# MCU.net
KiCad netlist of a schematic drawn in Altium Designer
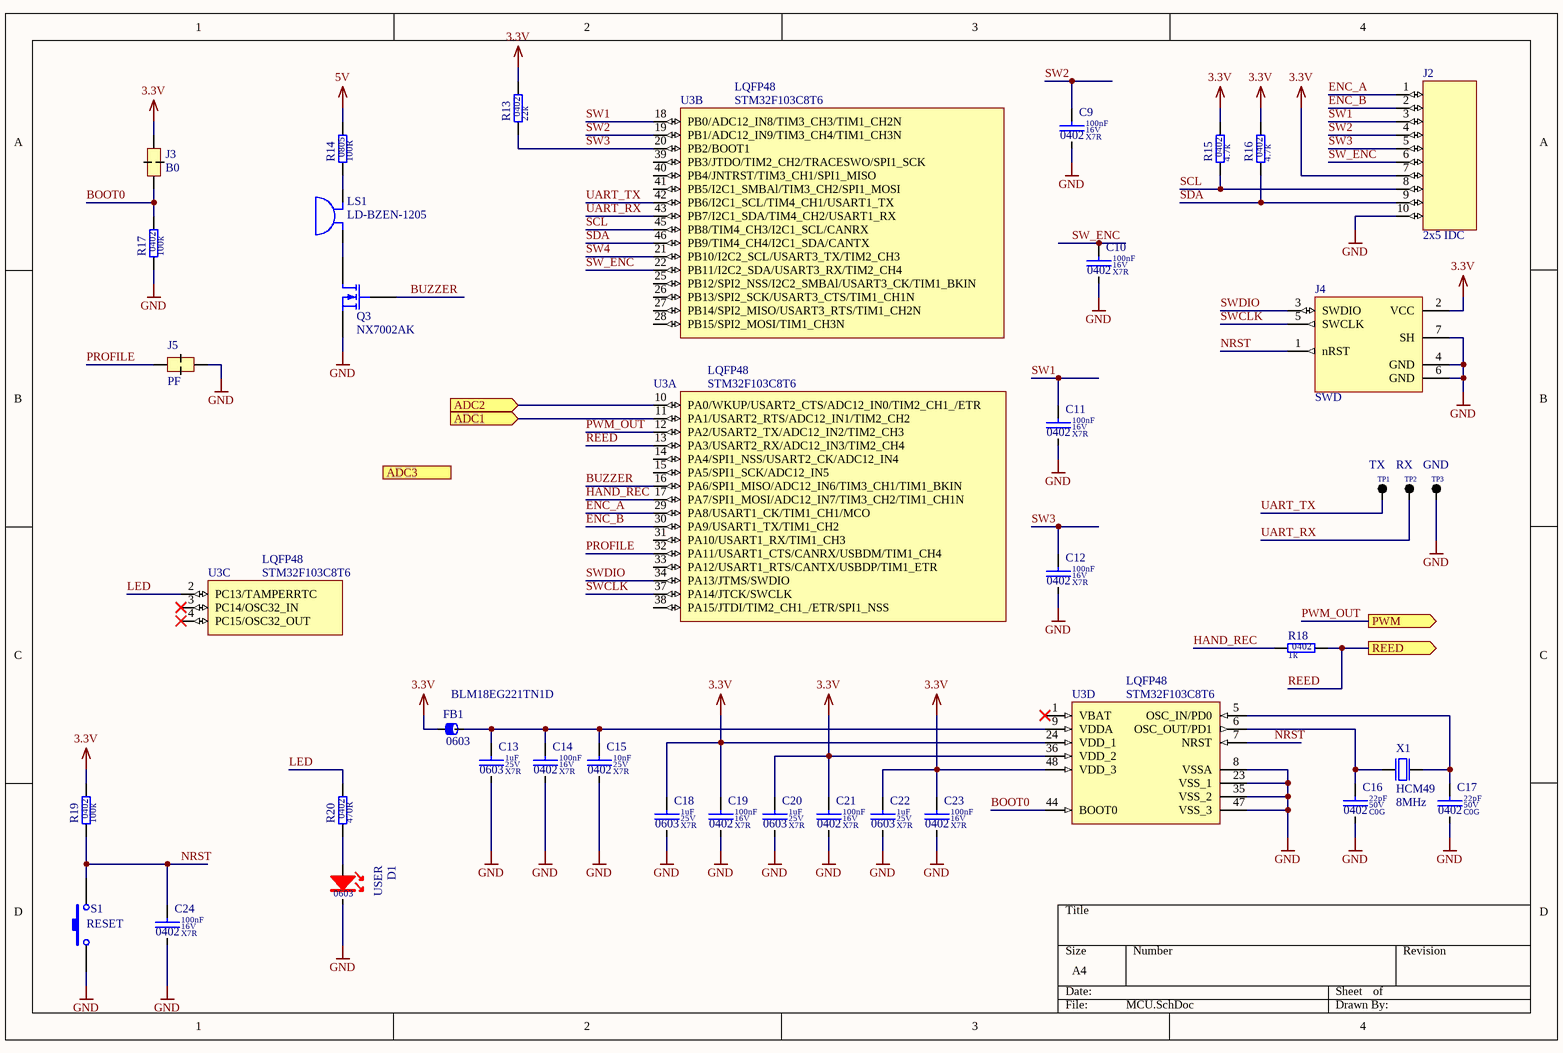
[diagram p0: MCU.SchDoc]

(export (version "E")
  (design (tool "Eeschema 10.0.6"))
  (components
    (comp (ref "C9")
      (value "100nF")
      (footprint "C_0402_1005")
      (description "Capacitor")
      (fields
        (field (name "DIELECTRIC") "X7R")
        (field (name "VOLTAGE") "16V")
        (field (name "SCH_FOOTPRINT") "0402")
        (field (name "PART NUMBER") "C_100nF_16V_X7R_0402_10")
        (field (name "MANUFACTURER") "Murata")
      )
      (libsource (lib "Library") (part "C"))
    )
    (comp (ref "C10")
      (value "100nF")
      (footprint "C_0402_1005")
      (description "Capacitor")
      (fields
        (field (name "DIELECTRIC") "X7R")
        (field (name "VOLTAGE") "16V")
        (field (name "SCH_FOOTPRINT") "0402")
        (field (name "PART NUMBER") "C_100nF_16V_X7R_0402_10")
        (field (name "MANUFACTURER") "Murata")
      )
      (libsource (lib "Library") (part "C"))
    )
    (comp (ref "C11")
      (value "100nF")
      (footprint "C_0402_1005")
      (description "Capacitor")
      (fields
        (field (name "DIELECTRIC") "X7R")
        (field (name "VOLTAGE") "16V")
        (field (name "SCH_FOOTPRINT") "0402")
        (field (name "PART NUMBER") "C_100nF_16V_X7R_0402_10")
        (field (name "MANUFACTURER") "Murata")
      )
      (libsource (lib "Library") (part "C"))
    )
    (comp (ref "C12")
      (value "100nF")
      (footprint "C_0402_1005")
      (description "Capacitor")
      (fields
        (field (name "DIELECTRIC") "X7R")
        (field (name "VOLTAGE") "16V")
        (field (name "SCH_FOOTPRINT") "0402")
        (field (name "PART NUMBER") "C_100nF_16V_X7R_0402_10")
        (field (name "MANUFACTURER") "Murata")
      )
      (libsource (lib "Library") (part "C"))
    )
    (comp (ref "C13")
      (value "1uF")
      (footprint "C_0603_1608")
      (description "Capacitor")
      (fields
        (field (name "DIELECTRIC") "X7R")
        (field (name "VOLTAGE") "25V")
        (field (name "SCH_FOOTPRINT") "0603")
        (field (name "PART NUMBER") "C_1uF_25V_X7R_0603_10")
        (field (name "MANUFACTURER") "Samsung")
      )
      (libsource (lib "Library") (part "C"))
    )
    (comp (ref "C14")
      (value "100nF")
      (footprint "C_0402_1005")
      (description "Capacitor")
      (fields
        (field (name "DIELECTRIC") "X7R")
        (field (name "VOLTAGE") "16V")
        (field (name "SCH_FOOTPRINT") "0402")
        (field (name "PART NUMBER") "C_100nF_16V_X7R_0402_10")
        (field (name "MANUFACTURER") "Murata")
      )
      (libsource (lib "Library") (part "C"))
    )
    (comp (ref "C15")
      (value "10nF")
      (footprint "C_0402_1005")
      (description "Capacitor")
      (fields
        (field (name "DIELECTRIC") "X7R")
        (field (name "VOLTAGE") "25V")
        (field (name "SCH_FOOTPRINT") "0402")
        (field (name "PART NUMBER") "C_10nF_25V_X7R_0402_10")
        (field (name "MANUFACTURER") "Murata")
      )
      (libsource (lib "Library") (part "C"))
    )
    (comp (ref "C16")
      (value "22pF")
      (footprint "C_0402_1005")
      (description "Capacitor")
      (fields
        (field (name "DIELECTRIC") "C0G")
        (field (name "VOLTAGE") "50V")
        (field (name "SCH_FOOTPRINT") "0402")
        (field (name "PART NUMBER") "C_22pF_50V_C0G_0402_5")
        (field (name "MANUFACTURER") "AVX")
      )
      (libsource (lib "Library") (part "C"))
    )
    (comp (ref "C17")
      (value "22pF")
      (footprint "C_0402_1005")
      (description "Capacitor")
      (fields
        (field (name "DIELECTRIC") "C0G")
        (field (name "VOLTAGE") "50V")
        (field (name "SCH_FOOTPRINT") "0402")
        (field (name "PART NUMBER") "C_22pF_50V_C0G_0402_5")
        (field (name "MANUFACTURER") "AVX")
      )
      (libsource (lib "Library") (part "C"))
    )
    (comp (ref "C18")
      (value "1uF")
      (footprint "C_0603_1608")
      (description "Capacitor")
      (fields
        (field (name "DIELECTRIC") "X7R")
        (field (name "VOLTAGE") "25V")
        (field (name "SCH_FOOTPRINT") "0603")
        (field (name "PART NUMBER") "C_1uF_25V_X7R_0603_10")
        (field (name "MANUFACTURER") "Samsung")
      )
      (libsource (lib "Library") (part "C"))
    )
    (comp (ref "C19")
      (value "100nF")
      (footprint "C_0402_1005")
      (description "Capacitor")
      (fields
        (field (name "DIELECTRIC") "X7R")
        (field (name "VOLTAGE") "16V")
        (field (name "SCH_FOOTPRINT") "0402")
        (field (name "PART NUMBER") "C_100nF_16V_X7R_0402_10")
        (field (name "MANUFACTURER") "Murata")
      )
      (libsource (lib "Library") (part "C"))
    )
    (comp (ref "C20")
      (value "1uF")
      (footprint "C_0603_1608")
      (description "Capacitor")
      (fields
        (field (name "DIELECTRIC") "X7R")
        (field (name "VOLTAGE") "25V")
        (field (name "SCH_FOOTPRINT") "0603")
        (field (name "PART NUMBER") "C_1uF_25V_X7R_0603_10")
        (field (name "MANUFACTURER") "Samsung")
      )
      (libsource (lib "Library") (part "C"))
    )
    (comp (ref "C21")
      (value "100nF")
      (footprint "C_0402_1005")
      (description "Capacitor")
      (fields
        (field (name "DIELECTRIC") "X7R")
        (field (name "VOLTAGE") "16V")
        (field (name "SCH_FOOTPRINT") "0402")
        (field (name "PART NUMBER") "C_100nF_16V_X7R_0402_10")
        (field (name "MANUFACTURER") "Murata")
      )
      (libsource (lib "Library") (part "C"))
    )
    (comp (ref "C22")
      (value "1uF")
      (footprint "C_0603_1608")
      (description "Capacitor")
      (fields
        (field (name "DIELECTRIC") "X7R")
        (field (name "VOLTAGE") "25V")
        (field (name "SCH_FOOTPRINT") "0603")
        (field (name "PART NUMBER") "C_1uF_25V_X7R_0603_10")
        (field (name "MANUFACTURER") "Samsung")
      )
      (libsource (lib "Library") (part "C"))
    )
    (comp (ref "C23")
      (value "100nF")
      (footprint "C_0402_1005")
      (description "Capacitor")
      (fields
        (field (name "DIELECTRIC") "X7R")
        (field (name "VOLTAGE") "16V")
        (field (name "SCH_FOOTPRINT") "0402")
        (field (name "PART NUMBER") "C_100nF_16V_X7R_0402_10")
        (field (name "MANUFACTURER") "Murata")
      )
      (libsource (lib "Library") (part "C"))
    )
    (comp (ref "C24")
      (value "100nF")
      (footprint "C_0402_1005")
      (description "Capacitor")
      (fields
        (field (name "DIELECTRIC") "X7R")
        (field (name "VOLTAGE") "16V")
        (field (name "SCH_FOOTPRINT") "0402")
        (field (name "PART NUMBER") "C_100nF_16V_X7R_0402_10")
        (field (name "MANUFACTURER") "Murata")
      )
      (libsource (lib "Library") (part "C"))
    )
    (comp (ref "D1")
      (value "USER")
      (footprint "OL_0603_1608")
      (description "LED_RED")
      (fields
        (field (name "SCH_FOOTPRINT") "0603")
        (field (name "PART NUMBER") "OL_R_0603")
        (field (name "MANUFACTURER") "Lite-On")
      )
      (libsource (lib "Library") (part "OL_R"))
    )
    (comp (ref "FB1")
      (value "BLM18EG221TN1D")
      (footprint "FB_0603_1608")
      (description "Ferrite Bead")
      (fields
        (field (name "PART NUMBER") "FB_BLM18EG221TN1D")
        (field (name "SCH_FOOTPRINT") "0603")
        (field (name "MANUFACTURER") "Murata")
      )
      (libsource (lib "Library") (part "FB"))
    )
    (comp (ref "J2")
      (value "2x5 IDC")
      (footprint "IDC 2x5 EDGE")
      (description "2x5 IDC Header")
      (libsource (lib "Lib - Connectors") (part "IDC_2x5"))
    )
    (comp (ref "J3")
      (value "B0")
      (footprint "SOLDER BRIDGE 0402")
      (description "Solder Bridge Jumper")
      (libsource (lib "Lib - Connectors") (part "Solder Bridge"))
    )
    (comp (ref "J4")
      (value "SWD")
      (footprint "TagConnectSWD")
      (description "TagConnect and 1.27mm IDC SWD Header")
      (libsource (lib "Lib - Connectors") (part "TagConnectSWD"))
    )
    (comp (ref "J5")
      (value "PF")
      (footprint "SOLDER BRIDGE 0402")
      (description "Solder Bridge Jumper")
      (libsource (lib "") (part "Solder Bridge_1"))
    )
    (comp (ref "LS1")
      (value "LD-BZEN-1205")
      (footprint "LD-BZEN-1205")
      (description "Przetwornik dźwięku: elektromagnetyczny; THT; 2,4kHz; 40mA; H: 9mm")
      (libsource (lib "soldering_station") (part "LD-BZEN-1205"))
    )
    (comp (ref "Q3")
      (value "NX7002AK")
      (footprint "NX7002AK.215")
      (description "Tranzystor: N-MOSFET; unipolarny; 60V; 0,12A; 325mW; SOT23")
      (libsource (lib "soldering_station") (part "NX7002AK.215"))
    )
    (comp (ref "R13")
      (value "22k")
      (footprint "R_0402_1005")
      (fields
        (field (name "SCH_FOOTPRINT") "0402")
        (field (name "PART NUMBER") "R_22k_0402_1")
        (field (name "VOLTAGE") "50V")
        (field (name "POWER") "63mW")
      )
      (libsource (lib "Library") (part "R"))
    )
    (comp (ref "R14")
      (value "100R")
      (footprint "R_0805_2012")
      (fields
        (field (name "SCH_FOOTPRINT") "0805")
        (field (name "PART NUMBER") "R_100R_0805_1")
        (field (name "VOLTAGE") "150V")
        (field (name "POWER") "125mW")
      )
      (libsource (lib "Library") (part "R"))
    )
    (comp (ref "R15")
      (value "4.7k")
      (footprint "R_0402_1005")
      (fields
        (field (name "SCH_FOOTPRINT") "0402")
        (field (name "PART NUMBER") "R_100k_0402_1")
        (field (name "VOLTAGE") "50V")
        (field (name "POWER") "63mW")
      )
      (libsource (lib "Library") (part "R"))
    )
    (comp (ref "R16")
      (value "4.7k")
      (footprint "R_0402_1005")
      (fields
        (field (name "SCH_FOOTPRINT") "0402")
        (field (name "PART NUMBER") "R_100k_0402_1")
        (field (name "VOLTAGE") "50V")
        (field (name "POWER") "63mW")
      )
      (libsource (lib "Library") (part "R"))
    )
    (comp (ref "R17")
      (value "100k")
      (footprint "R_0402_1005")
      (fields
        (field (name "SCH_FOOTPRINT") "0402")
        (field (name "PART NUMBER") "R_100k_0402_1")
        (field (name "VOLTAGE") "50V")
        (field (name "POWER") "63mW")
      )
      (libsource (lib "Library") (part "R"))
    )
    (comp (ref "R18")
      (value "1k")
      (footprint "R_0402_1005")
      (fields
        (field (name "SCH_FOOTPRINT") "0402")
        (field (name "PART NUMBER") "R_1k_0402_1")
        (field (name "VOLTAGE") "50V")
        (field (name "POWER") "63mW")
      )
      (libsource (lib "Library") (part "R"))
    )
    (comp (ref "R19")
      (value "100k")
      (footprint "R_0402_1005")
      (fields
        (field (name "SCH_FOOTPRINT") "0402")
        (field (name "PART NUMBER") "R_100k_0402_1")
        (field (name "VOLTAGE") "50V")
        (field (name "POWER") "63mW")
      )
      (libsource (lib "Library") (part "R"))
    )
    (comp (ref "R20")
      (value "470R")
      (footprint "R_0402_1005")
      (fields
        (field (name "SCH_FOOTPRINT") "0402")
        (field (name "PART NUMBER") "R_470R_0402_1")
        (field (name "VOLTAGE") "50V")
        (field (name "POWER") "63mW")
      )
      (libsource (lib "Library") (part "R"))
    )
    (comp (ref "S1")
      (value "RESET")
      (footprint "S_TACTSWITCH3x6")
      (description "Tact Switch")
      (fields (field (name "PART NUMBER") "S_TACTSWITCH") (field (name "MANUFACTURER") "Ninigi"))
      (libsource (lib "Library") (part "S_TACTSWITCH"))
    )
    (comp (ref "TP1")
      (value "TX")
      (footprint "TP_PAD")
      (description "Testpoint")
      (fields (field (name "PART NUMBER") "TP_PAD"))
      (libsource (lib "Library") (part "TP_TESTPOINT"))
    )
    (comp (ref "TP2")
      (value "RX")
      (footprint "TP_PAD")
      (description "Testpoint")
      (fields (field (name "PART NUMBER") "TP_PAD"))
      (libsource (lib "Library") (part "TP_TESTPOINT"))
    )
    (comp (ref "TP3")
      (value "GND")
      (footprint "TP_PAD")
      (description "Testpoint")
      (fields (field (name "PART NUMBER") "TP_PAD"))
      (libsource (lib "Library") (part "TP_TESTPOINT"))
    )
    (comp (ref "U3")
      (value "STM32F103C8T6")
      (footprint "LQFP48_7x7")
      (fields
        (field (name "SCH_FOOTPRINT") "LQFP48")
        (field (name "PART NUMBER") "UP_STM32F103C8T6")
        (field (name "MANUFACTURER") "STMicroelectronics")
      )
      (libsource (lib "Library") (part "UP_STM32F103Cx"))
    )
    (comp (ref "X1")
      (value "8MHz")
      (footprint "X_HC49_SMD")
      (description "Resonator Ceramic")
      (fields
        (field (name "SCH_FOOTPRINT") "HCM49")
        (field (name "PART NUMBER") "X_6MHz_HCM49")
        (field (name "MANUFACTURER PART NUMBER") "LF XTAL016788")
      )
      (libsource (lib "Library") (part "X_GENERIC"))
    )
  )
  (nets
    (net (code "1") (name "/ADC1") (class "Default")
      (node (ref "U3") (pin "11") (pinfunction "PA1/USART2_RTS/ADC12_IN1/TIM2_CH2_11") (pintype "bidirectional"))
    )
    (net (code "2") (name "/ADC2") (class "Default")
      (node (ref "U3") (pin "10") (pinfunction "PA0/WKUP/USART2_CTS/ADC12_IN0/TIM2_CH1_/ETR_10") (pintype "bidirectional"))
    )
    (net (code "4") (name "/BOOT0") (class "Default")
      (node (ref "J3") (pin "2") (pinfunction "2_2") (pintype "passive"))
      (node (ref "R17") (pin "2") (pinfunction "2_2") (pintype "passive"))
      (node (ref "U3") (pin "44") (pinfunction "BOOT0_44") (pintype "input"))
    )
    (net (code "5") (name "/BUZZER") (class "Default")
      (node (ref "Q3") (pin "1") (pinfunction "G_1") (pintype "passive"))
      (node (ref "U3") (pin "16") (pinfunction "PA6/SPI1_MISO/ADC12_IN6/TIM3_CH1/TIM1_BKIN_16") (pintype "bidirectional"))
    )
    (net (code "6") (name "/ENC_A") (class "Default")
      (node (ref "J2") (pin "1") (pintype "bidirectional"))
      (node (ref "U3") (pin "29") (pinfunction "PA8/USART1_CK/TIM1_CH1/MCO_29") (pintype "bidirectional"))
    )
    (net (code "7") (name "/ENC_B") (class "Default")
      (node (ref "J2") (pin "2") (pintype "bidirectional"))
      (node (ref "U3") (pin "30") (pinfunction "PA9/USART1_TX/TIM1_CH2_30") (pintype "bidirectional"))
    )
    (net (code "8") (name "/HAND_REC") (class "Default")
      (node (ref "R18") (pin "1") (pinfunction "1_1") (pintype "passive"))
      (node (ref "U3") (pin "17") (pinfunction "PA7/SPI1_MOSI/ADC12_IN7/TIM3_CH2/TIM1_CH1N_17") (pintype "bidirectional"))
    )
    (net (code "9") (name "/LED") (class "Default")
      (node (ref "R20") (pin "2") (pinfunction "2_2") (pintype "passive"))
      (node (ref "U3") (pin "2") (pinfunction "PC13/TAMPERRTC_2") (pintype "bidirectional"))
    )
    (net (code "10") (name "/NRST") (class "Default")
      (node (ref "C24") (pin "1") (pinfunction "1_1") (pintype "passive"))
      (node (ref "J4") (pin "1") (pinfunction "nRST_1") (pintype "output"))
      (node (ref "R19") (pin "1") (pinfunction "1_1") (pintype "passive"))
      (node (ref "S1") (pin "2") (pinfunction "2_2") (pintype "passive"))
      (node (ref "U3") (pin "7") (pinfunction "NRST_7") (pintype "input"))
    )
    (net (code "11") (name "/PROFILE") (class "Default")
      (node (ref "J5") (pin "2") (pinfunction "2_2") (pintype "passive"))
      (node (ref "U3") (pin "32") (pinfunction "PA11/USART1_CTS/CANRX/USBDM/TIM1_CH4_32") (pintype "bidirectional"))
    )
    (net (code "12") (name "/PWM_OUT") (class "Default")
      (node (ref "U3") (pin "12") (pinfunction "PA2/USART2_TX/ADC12_IN2/TIM2_CH3_12") (pintype "bidirectional"))
    )
    (net (code "13") (name "/REED") (class "Default")
      (node (ref "R18") (pin "2") (pinfunction "2_2") (pintype "passive"))
      (node (ref "U3") (pin "13") (pinfunction "PA3/USART2_RX/ADC12_IN3/TIM2_CH4_13") (pintype "bidirectional"))
    )
    (net (code "14") (name "/SCL") (class "Default")
      (node (ref "J2") (pin "8") (pintype "bidirectional"))
      (node (ref "R15") (pin "1") (pinfunction "1_1") (pintype "passive"))
      (node (ref "U3") (pin "45") (pinfunction "PB8/TIM4_CH3/I2C1_SCL/CANRX_45") (pintype "bidirectional"))
    )
    (net (code "15") (name "/SDA") (class "Default")
      (node (ref "J2") (pin "9") (pintype "bidirectional"))
      (node (ref "R16") (pin "1") (pinfunction "1_1") (pintype "passive"))
      (node (ref "U3") (pin "46") (pinfunction "PB9/TIM4_CH4/I2C1_SDA/CANTX_46") (pintype "bidirectional"))
    )
    (net (code "16") (name "/SW1") (class "Default")
      (node (ref "C11") (pin "1") (pinfunction "1_1") (pintype "passive"))
      (node (ref "J2") (pin "3") (pintype "bidirectional"))
      (node (ref "U3") (pin "18") (pinfunction "PB0/ADC12_IN8/TIM3_CH3/TIM1_CH2N_18") (pintype "bidirectional"))
    )
    (net (code "17") (name "/SW2") (class "Default")
      (node (ref "C9") (pin "1") (pinfunction "1_1") (pintype "passive"))
      (node (ref "J2") (pin "4") (pintype "bidirectional"))
      (node (ref "U3") (pin "19") (pinfunction "PB1/ADC12_IN9/TIM3_CH4/TIM1_CH3N_19") (pintype "bidirectional"))
    )
    (net (code "18") (name "/SW3") (class "Default")
      (node (ref "C12") (pin "1") (pinfunction "1_1") (pintype "passive"))
      (node (ref "J2") (pin "5") (pintype "bidirectional"))
      (node (ref "R13") (pin "1") (pinfunction "1_1") (pintype "passive"))
      (node (ref "U3") (pin "20") (pinfunction "PB2/BOOT1_20") (pintype "bidirectional"))
    )
    (net (code "19") (name "/SW4") (class "Default")
      (node (ref "U3") (pin "21") (pinfunction "PB10/I2C2_SCL/USART3_TX/TIM2_CH3_21") (pintype "bidirectional"))
    )
    (net (code "20") (name "/SWCLK") (class "Default")
      (node (ref "J4") (pin "5") (pinfunction "SWCLK_5") (pintype "output"))
      (node (ref "U3") (pin "37") (pinfunction "PA14/JTCK/SWCLK_37") (pintype "bidirectional"))
    )
    (net (code "21") (name "/SWDIO") (class "Default")
      (node (ref "J4") (pin "3") (pinfunction "SWDIO_3") (pintype "bidirectional"))
      (node (ref "U3") (pin "34") (pinfunction "PA13/JTMS/SWDIO_34") (pintype "bidirectional"))
    )
    (net (code "22") (name "/SW_ENC") (class "Default")
      (node (ref "C10") (pin "1") (pinfunction "1_1") (pintype "passive"))
      (node (ref "J2") (pin "6") (pintype "bidirectional"))
      (node (ref "U3") (pin "22") (pinfunction "PB11/I2C2_SDA/USART3_RX/TIM2_CH4_22") (pintype "bidirectional"))
    )
    (net (code "23") (name "/UART_RX") (class "Default")
      (node (ref "TP2") (pin "1") (pinfunction "TP_1") (pintype "passive"))
      (node (ref "U3") (pin "43") (pinfunction "PB7/I2C1_SDA/TIM4_CH2/USART1_RX_43") (pintype "bidirectional"))
    )
    (net (code "24") (name "/UART_TX") (class "Default")
      (node (ref "TP1") (pin "1") (pinfunction "TP_1") (pintype "passive"))
      (node (ref "U3") (pin "42") (pinfunction "PB6/I2C1_SCL/TIM4_CH1/USART1_TX_42") (pintype "bidirectional"))
    )
    (net (code "25") (name "3.3V") (class "Default")
      (node (ref "C18") (pin "1") (pinfunction "1_1") (pintype "passive"))
      (node (ref "C19") (pin "1") (pinfunction "1_1") (pintype "passive"))
      (node (ref "C20") (pin "1") (pinfunction "1_1") (pintype "passive"))
      (node (ref "C21") (pin "1") (pinfunction "1_1") (pintype "passive"))
      (node (ref "C22") (pin "1") (pinfunction "1_1") (pintype "passive"))
      (node (ref "C23") (pin "1") (pinfunction "1_1") (pintype "passive"))
      (node (ref "FB1") (pin "1") (pintype "passive"))
      (node (ref "J2") (pin "7") (pintype "bidirectional"))
      (node (ref "J3") (pin "1") (pinfunction "1_1") (pintype "passive"))
      (node (ref "J4") (pin "2") (pinfunction "VCC_2") (pintype "power_in"))
      (node (ref "R13") (pin "2") (pinfunction "2_2") (pintype "passive"))
      (node (ref "R15") (pin "2") (pinfunction "2_2") (pintype "passive"))
      (node (ref "R16") (pin "2") (pinfunction "2_2") (pintype "passive"))
      (node (ref "R19") (pin "2") (pinfunction "2_2") (pintype "passive"))
      (node (ref "U3") (pin "24") (pinfunction "VDD_1_24") (pintype "input"))
      (node (ref "U3") (pin "36") (pinfunction "VDD_2_36") (pintype "input"))
      (node (ref "U3") (pin "48") (pinfunction "VDD_3_48") (pintype "input"))
    )
    (net (code "26") (name "5V") (class "Default")
      (node (ref "R14") (pin "2") (pinfunction "2_2") (pintype "passive"))
    )
    (net (code "27") (name "GND") (class "Default")
      (node (ref "C10") (pin "2") (pinfunction "2_2") (pintype "passive"))
      (node (ref "C11") (pin "2") (pinfunction "2_2") (pintype "passive"))
      (node (ref "C12") (pin "2") (pinfunction "2_2") (pintype "passive"))
      (node (ref "C13") (pin "2") (pinfunction "2_2") (pintype "passive"))
      (node (ref "C14") (pin "2") (pinfunction "2_2") (pintype "passive"))
      (node (ref "C15") (pin "2") (pinfunction "2_2") (pintype "passive"))
      (node (ref "C16") (pin "2") (pinfunction "2_2") (pintype "passive"))
      (node (ref "C17") (pin "2") (pinfunction "2_2") (pintype "passive"))
      (node (ref "C18") (pin "2") (pinfunction "2_2") (pintype "passive"))
      (node (ref "C19") (pin "2") (pinfunction "2_2") (pintype "passive"))
      (node (ref "C20") (pin "2") (pinfunction "2_2") (pintype "passive"))
      (node (ref "C21") (pin "2") (pinfunction "2_2") (pintype "passive"))
      (node (ref "C22") (pin "2") (pinfunction "2_2") (pintype "passive"))
      (node (ref "C23") (pin "2") (pinfunction "2_2") (pintype "passive"))
      (node (ref "C24") (pin "2") (pinfunction "2_2") (pintype "passive"))
      (node (ref "C9") (pin "2") (pinfunction "2_2") (pintype "passive"))
      (node (ref "D1") (pin "1") (pinfunction "K_1") (pintype "passive"))
      (node (ref "J2") (pin "10") (pintype "bidirectional"))
      (node (ref "J4") (pin "4") (pinfunction "GND_4") (pintype "power_in"))
      (node (ref "J4") (pin "6") (pinfunction "GND_6") (pintype "power_in"))
      (node (ref "J4") (pin "7") (pinfunction "SH_7") (pintype "passive"))
      (node (ref "J5") (pin "1") (pinfunction "1_1") (pintype "passive"))
      (node (ref "Q3") (pin "2") (pinfunction "S_2") (pintype "passive"))
      (node (ref "R17") (pin "1") (pinfunction "1_1") (pintype "passive"))
      (node (ref "S1") (pin "1") (pinfunction "1_1") (pintype "passive"))
      (node (ref "TP3") (pin "1") (pinfunction "TP_1") (pintype "passive"))
      (node (ref "U3") (pin "23") (pinfunction "VSS_1_23") (pintype "power_in"))
      (node (ref "U3") (pin "35") (pinfunction "VSS_2_35") (pintype "power_in"))
      (node (ref "U3") (pin "47") (pinfunction "VSS_3_47") (pintype "power_in"))
      (node (ref "U3") (pin "8") (pinfunction "VSSA_8") (pintype "power_in"))
    )
    (net (code "28") (name "Net-(D1-A)") (class "Default")
      (node (ref "D1") (pin "2") (pinfunction "A_2") (pintype "passive"))
      (node (ref "R20") (pin "1") (pinfunction "1_1") (pintype "passive"))
    )
    (net (code "29") (name "Net-(LS1-Pad1)") (class "Default")
      (node (ref "LS1") (pin "1") (pinfunction "1_1") (pintype "passive"))
      (node (ref "R14") (pin "1") (pinfunction "1_1") (pintype "passive"))
    )
    (net (code "30") (name "Net-(Q3-D)") (class "Default")
      (node (ref "LS1") (pin "2") (pinfunction "2_2") (pintype "passive"))
      (node (ref "Q3") (pin "3") (pinfunction "D_3") (pintype "passive"))
    )
    (net (code "31") (name "Net-(U3D-OSC_IN{slash}PD0)") (class "Default")
      (node (ref "C17") (pin "1") (pinfunction "1_1") (pintype "passive"))
      (node (ref "U3") (pin "5") (pinfunction "OSC_IN/PD0_5") (pintype "input"))
      (node (ref "X1") (pin "2") (pintype "passive"))
    )
    (net (code "32") (name "Net-(U3D-OSC_OUT{slash}PD1)") (class "Default")
      (node (ref "C16") (pin "1") (pinfunction "1_1") (pintype "passive"))
      (node (ref "U3") (pin "6") (pinfunction "OSC_OUT/PD1_6") (pintype "output"))
      (node (ref "X1") (pin "1") (pintype "passive"))
    )
    (net (code "33") (name "Net-(U3D-VDDA)") (class "Default")
      (node (ref "C13") (pin "1") (pinfunction "1_1") (pintype "passive"))
      (node (ref "C14") (pin "1") (pinfunction "1_1") (pintype "passive"))
      (node (ref "C15") (pin "1") (pinfunction "1_1") (pintype "passive"))
      (node (ref "FB1") (pin "2") (pintype "passive"))
      (node (ref "U3") (pin "9") (pinfunction "VDDA_9") (pintype "input"))
    )
    (net (code "34") (name "unconnected-(U3A-PA4{slash}SPI1_NSS{slash}USART2_CK{slash}ADC12_IN4-Pad14)") (class "Default")
      (node (ref "U3") (pin "14") (pinfunction "PA4/SPI1_NSS/USART2_CK/ADC12_IN4_14") (pintype "bidirectional"))
    )
    (net (code "35") (name "unconnected-(U3A-PA5{slash}SPI1_SCK{slash}ADC12_IN5-Pad15)") (class "Default")
      (node (ref "U3") (pin "15") (pinfunction "PA5/SPI1_SCK/ADC12_IN5_15") (pintype "bidirectional"))
    )
    (net (code "36") (name "unconnected-(U3A-PA10{slash}USART1_RX{slash}TIM1_CH3-Pad31)") (class "Default")
      (node (ref "U3") (pin "31") (pinfunction "PA10/USART1_RX/TIM1_CH3_31") (pintype "bidirectional"))
    )
    (net (code "37") (name "unconnected-(U3A-PA12{slash}USART1_RTS{slash}CANTX{slash}USBDP{slash}TIM1_ETR-Pad33)") (class "Default")
      (node (ref "U3") (pin "33") (pinfunction "PA12/USART1_RTS/CANTX/USBDP/TIM1_ETR_33") (pintype "bidirectional"))
    )
    (net (code "38") (name "unconnected-(U3A-PA15{slash}JTDI{slash}TIM2_CH1_{slash}ETR{slash}SPI1_NSS-Pad38)") (class "Default")
      (node (ref "U3") (pin "38") (pinfunction "PA15/JTDI/TIM2_CH1_/ETR/SPI1_NSS_38") (pintype "bidirectional"))
    )
    (net (code "39") (name "unconnected-(U3B-PB3{slash}JTDO{slash}TIM2_CH2{slash}TRACESWO{slash}SPI1_SCK-Pad39)") (class "Default")
      (node (ref "U3") (pin "39") (pinfunction "PB3/JTDO/TIM2_CH2/TRACESWO/SPI1_SCK_39") (pintype "bidirectional"))
    )
    (net (code "40") (name "unconnected-(U3B-PB4{slash}JNTRST{slash}TIM3_CH1{slash}SPI1_MISO-Pad40)") (class "Default")
      (node (ref "U3") (pin "40") (pinfunction "PB4/JNTRST/TIM3_CH1/SPI1_MISO_40") (pintype "bidirectional"))
    )
    (net (code "41") (name "unconnected-(U3B-PB5{slash}I2C1_SMBAl{slash}TIM3_CH2{slash}SPI1_MOSI-Pad41)") (class "Default")
      (node (ref "U3") (pin "41") (pinfunction "PB5/I2C1_SMBAl/TIM3_CH2/SPI1_MOSI_41") (pintype "bidirectional"))
    )
    (net (code "42") (name "unconnected-(U3B-PB12{slash}SPI2_NSS{slash}I2C2_SMBAl{slash}USART3_CK{slash}TIM1_BKIN-Pad25)") (class "Default")
      (node (ref "U3") (pin "25") (pinfunction "PB12/SPI2_NSS/I2C2_SMBAl/USART3_CK/TIM1_BKIN_25") (pintype "bidirectional"))
    )
    (net (code "43") (name "unconnected-(U3B-PB13{slash}SPI2_SCK{slash}USART3_CTS{slash}TIM1_CH1N-Pad26)") (class "Default")
      (node (ref "U3") (pin "26") (pinfunction "PB13/SPI2_SCK/USART3_CTS/TIM1_CH1N_26") (pintype "bidirectional"))
    )
    (net (code "44") (name "unconnected-(U3B-PB14{slash}SPI2_MISO{slash}USART3_RTS{slash}TIM1_CH2N-Pad27)") (class "Default")
      (node (ref "U3") (pin "27") (pinfunction "PB14/SPI2_MISO/USART3_RTS/TIM1_CH2N_27") (pintype "bidirectional"))
    )
    (net (code "45") (name "unconnected-(U3B-PB15{slash}SPI2_MOSI{slash}TIM1_CH3N-Pad28)") (class "Default")
      (node (ref "U3") (pin "28") (pinfunction "PB15/SPI2_MOSI/TIM1_CH3N_28") (pintype "bidirectional"))
    )
    (net (code "46") (name "unconnected-(U3C-PC14{slash}OSC32_IN-Pad3)") (class "Default")
      (node (ref "U3") (pin "3") (pinfunction "PC14/OSC32_IN_3") (pintype "bidirectional+no_connect"))
    )
    (net (code "47") (name "unconnected-(U3C-PC15{slash}OSC32_OUT-Pad4)") (class "Default")
      (node (ref "U3") (pin "4") (pinfunction "PC15/OSC32_OUT_4") (pintype "bidirectional+no_connect"))
    )
    (net (code "48") (name "unconnected-(U3D-VBAT-Pad1)") (class "Default")
      (node (ref "U3") (pin "1") (pinfunction "VBAT_1") (pintype "input+no_connect"))
    )
  )
)
